# Oled_Display_and_Bluetooth_Sensor.net
KiCad netlist of a schematic drawn in Altium Designer
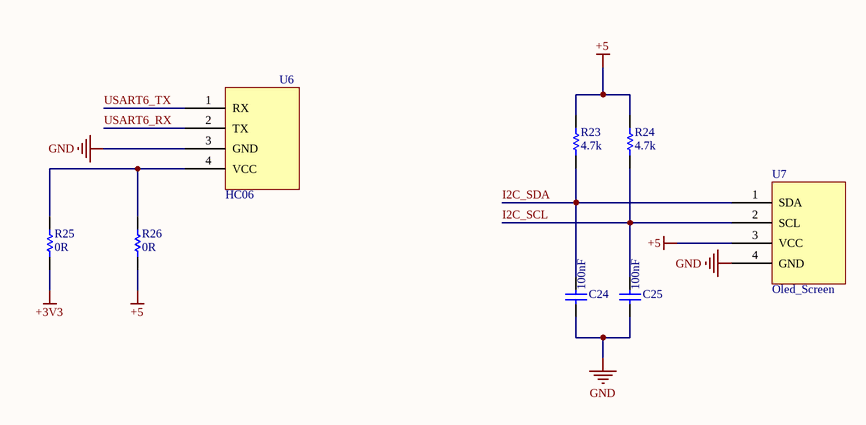
[diagram p0: Oled Display and Bluetooth Sensor.SchDoc]

(export (version "E")
  (design (tool "Eeschema 10.0.6"))
  (components
    (comp (ref "C24")
      (value "100nF")
      (footprint "CAPC2013X135X45LL10T25")
      (fields (field (name "MANUFACTURER") "Murata") (field (name "PART NUMBER") "GRM21BR71H105KA12L"))
      (libsource (lib "Altium Content Vault") (part "CAP"))
    )
    (comp (ref "C25")
      (value "100nF")
      (footprint "CAPC2013X135X45LL10T25")
      (fields (field (name "MANUFACTURER") "Murata") (field (name "PART NUMBER") "GRM21BR71H105KA12L"))
      (libsource (lib "Altium Content Vault") (part "CAP"))
    )
    (comp (ref "R23")
      (value "4.7k")
      (footprint "RESC2013X70X40NL20T20")
      (fields (field (name "PART NUMBER") "ERJ6ENF47R0V") (field (name "MANUFACTURER") "Panasonic"))
      (libsource (lib "Altium Content Vault") (part "RES"))
    )
    (comp (ref "R24")
      (value "4.7k")
      (footprint "RESC2013X70X40NL20T20")
      (fields (field (name "PART NUMBER") "ERJ6ENF47R0V") (field (name "MANUFACTURER") "Panasonic"))
      (libsource (lib "Altium Content Vault") (part "RES"))
    )
    (comp (ref "R25")
      (value "0R")
      (footprint "RESC2013X70X40NL20T20")
      (fields (field (name "PART NUMBER") "ERJ6ENF47R0V") (field (name "MANUFACTURER") "Panasonic"))
      (libsource (lib "Altium Content Vault") (part "RES"))
    )
    (comp (ref "R26")
      (value "0R")
      (footprint "RESC2013X70X40NL20T20")
      (fields (field (name "PART NUMBER") "ERJ6ENF47R0V") (field (name "MANUFACTURER") "Panasonic"))
      (libsource (lib "Altium Content Vault") (part "RES"))
    )
    (comp (ref "U6")
      (value "HC06")
      (footprint "HC06")
      (description "HC06 Bluetooth Sensor")
      (libsource (lib "User_Library") (part "HC06"))
    )
    (comp (ref "U7")
      (value "Oled_Screen")
      (footprint "Oled_Ekran")
      (description "I2C Communication 0.96inch 5V Oled Screen")
      (libsource (lib "User_Library") (part "Oled Ekran"))
    )
  )
  (nets
    (net (code "1") (name "+3V3") (class "Default")
      (node (ref "R25") (pin "2") (pinfunction "2_2") (pintype "passive"))
    )
    (net (code "2") (name "+5") (class "Default")
      (node (ref "R23") (pin "1") (pinfunction "1_1") (pintype "passive"))
      (node (ref "R24") (pin "1") (pinfunction "1_1") (pintype "passive"))
      (node (ref "R26") (pin "2") (pinfunction "2_2") (pintype "passive"))
      (node (ref "U7") (pin "3") (pinfunction "VCC_3") (pintype "power_in"))
    )
    (net (code "3") (name "/I2C_SCL") (class "Default")
      (node (ref "C25") (pin "2") (pinfunction "2_2") (pintype "passive"))
      (node (ref "R24") (pin "2") (pinfunction "2_2") (pintype "passive"))
      (node (ref "U7") (pin "2") (pinfunction "SCL_2") (pintype "power_in"))
    )
    (net (code "4") (name "/I2C_SDA") (class "Default")
      (node (ref "C24") (pin "2") (pinfunction "2_2") (pintype "passive"))
      (node (ref "R23") (pin "2") (pinfunction "2_2") (pintype "passive"))
      (node (ref "U7") (pin "1") (pinfunction "SDA_1") (pintype "power_in"))
    )
    (net (code "5") (name "/USART6_RX") (class "Default")
      (node (ref "U6") (pin "2") (pinfunction "TX_2") (pintype "power_in"))
    )
    (net (code "6") (name "/USART6_TX") (class "Default")
      (node (ref "U6") (pin "1") (pinfunction "RX_1") (pintype "power_in"))
    )
    (net (code "7") (name "GND") (class "Default")
      (node (ref "C24") (pin "1") (pinfunction "1_1") (pintype "passive"))
      (node (ref "C25") (pin "1") (pinfunction "1_1") (pintype "passive"))
      (node (ref "U6") (pin "3") (pinfunction "GND_3") (pintype "power_in"))
      (node (ref "U7") (pin "4") (pinfunction "GND_4") (pintype "power_in"))
    )
    (net (code "8") (name "Net-(U6-VCC)") (class "Default")
      (node (ref "R25") (pin "1") (pinfunction "1_1") (pintype "passive"))
      (node (ref "R26") (pin "1") (pinfunction "1_1") (pintype "passive"))
      (node (ref "U6") (pin "4") (pinfunction "VCC_4") (pintype "power_in"))
    )
  )
)
